# 1wire_connection_board.net
KiCad netlist of a schematic drawn in EAGLE
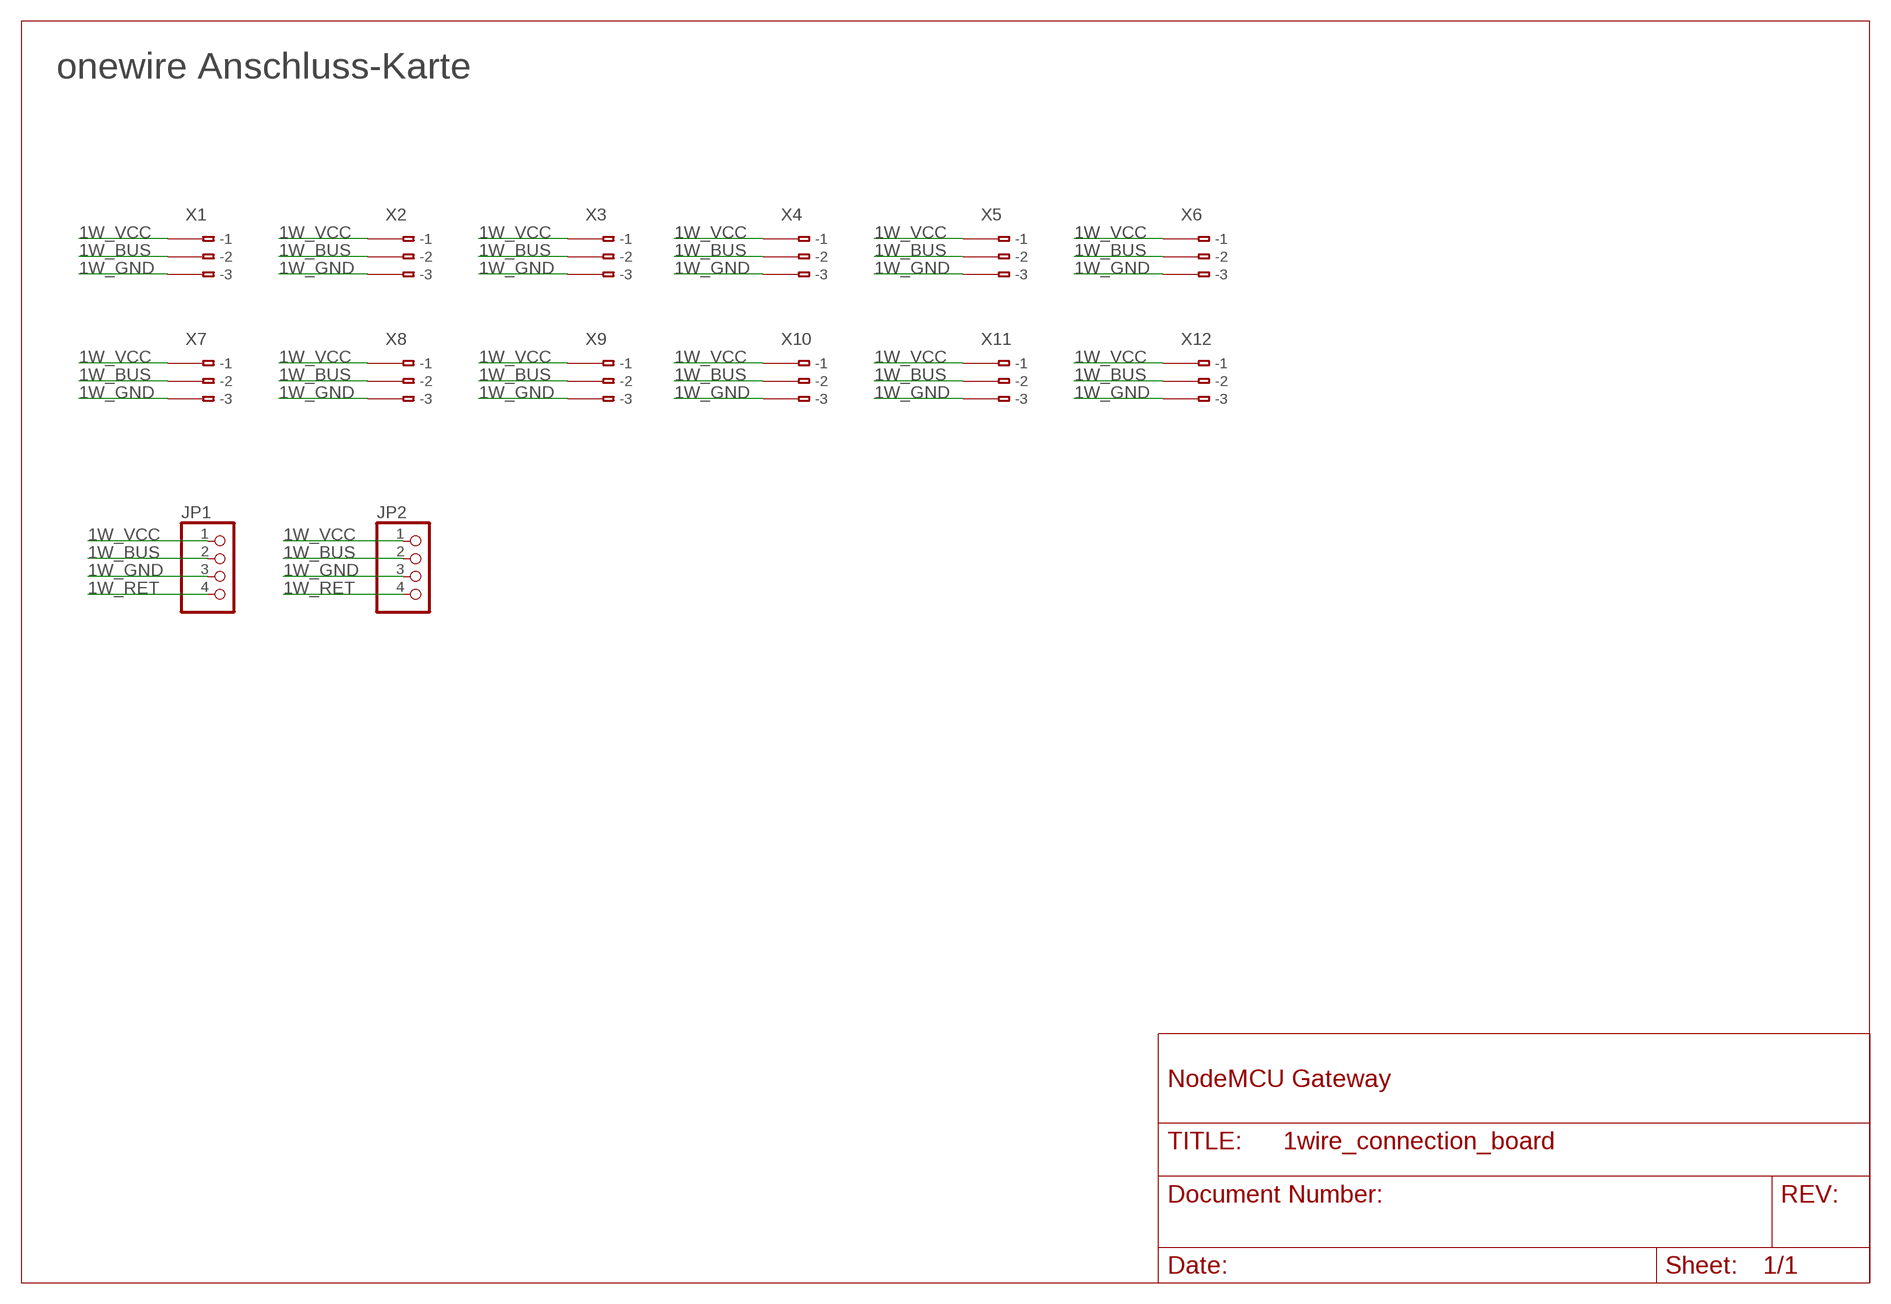
[diagram p0: schematic, sheet 1]

(export (version "E")
  (design (tool "Eeschema 10.0.6"))
  (components
    (comp (ref "JP1")
      (value "PINHD-1X4_S")
      (footprint "eagle-import:1X04")
      (libsource (lib "eagle-import") (part "PINHD-1X4_S"))
    )
    (comp (ref "JP2")
      (value "PINHD-1X4_S")
      (footprint "eagle-import:1X04")
      (libsource (lib "eagle-import") (part "PINHD-1X4_S"))
    )
    (comp (ref "X1")
      (value "CON_350-103")
      (footprint "eagle-import:CON_350-103")
      (fields (field (name "MPN") "233-103"))
      (libsource (lib "eagle-import") (part "CON_350-103"))
    )
    (comp (ref "X2")
      (value "CON_350-103OHNE_RAND")
      (footprint "eagle-import:CON_350-103_O")
      (libsource (lib "eagle-import") (part "CON_350-103OHNE_RAND"))
    )
    (comp (ref "X3")
      (value "CON_350-103OHNE_RAND")
      (footprint "eagle-import:CON_350-103_O")
      (libsource (lib "eagle-import") (part "CON_350-103OHNE_RAND"))
    )
    (comp (ref "X4")
      (value "CON_350-103OHNE_RAND")
      (footprint "eagle-import:CON_350-103_O")
      (libsource (lib "eagle-import") (part "CON_350-103OHNE_RAND"))
    )
    (comp (ref "X5")
      (value "CON_350-103OHNE_RAND")
      (footprint "eagle-import:CON_350-103_O")
      (libsource (lib "eagle-import") (part "CON_350-103OHNE_RAND"))
    )
    (comp (ref "X6")
      (value "CON_350-103OHNE_RAND")
      (footprint "eagle-import:CON_350-103_O")
      (libsource (lib "eagle-import") (part "CON_350-103OHNE_RAND"))
    )
    (comp (ref "X7")
      (value "CON_350-103")
      (footprint "eagle-import:CON_350-103")
      (fields (field (name "MPN") "233-103"))
      (libsource (lib "eagle-import") (part "CON_350-103"))
    )
    (comp (ref "X8")
      (value "CON_350-103OHNE_RAND")
      (footprint "eagle-import:CON_350-103_O")
      (libsource (lib "eagle-import") (part "CON_350-103OHNE_RAND"))
    )
    (comp (ref "X9")
      (value "CON_350-103OHNE_RAND")
      (footprint "eagle-import:CON_350-103_O")
      (libsource (lib "eagle-import") (part "CON_350-103OHNE_RAND"))
    )
    (comp (ref "X10")
      (value "CON_350-103OHNE_RAND")
      (footprint "eagle-import:CON_350-103_O")
      (libsource (lib "eagle-import") (part "CON_350-103OHNE_RAND"))
    )
    (comp (ref "X11")
      (value "CON_350-103OHNE_RAND")
      (footprint "eagle-import:CON_350-103_O")
      (libsource (lib "eagle-import") (part "CON_350-103OHNE_RAND"))
    )
    (comp (ref "X12")
      (value "CON_350-103OHNE_RAND")
      (footprint "eagle-import:CON_350-103_O")
      (libsource (lib "eagle-import") (part "CON_350-103OHNE_RAND"))
    )
  )
  (nets
    (net (code "1") (name "/1W_BUS") (class "Default")
      (node (ref "JP1") (pin "2") (pinfunction "2_2") (pintype "passive"))
      (node (ref "JP2") (pin "2") (pinfunction "2_2") (pintype "passive"))
      (node (ref "X1") (pin "B2") (pinfunction "B-2_B2") (pintype "passive"))
      (node (ref "X10") (pin "B2") (pinfunction "B-2_B2") (pintype "passive"))
      (node (ref "X11") (pin "B2") (pinfunction "B-2_B2") (pintype "passive"))
      (node (ref "X12") (pin "B2") (pinfunction "B-2_B2") (pintype "passive"))
      (node (ref "X2") (pin "B2") (pinfunction "B-2_B2") (pintype "passive"))
      (node (ref "X3") (pin "B2") (pinfunction "B-2_B2") (pintype "passive"))
      (node (ref "X4") (pin "B2") (pinfunction "B-2_B2") (pintype "passive"))
      (node (ref "X5") (pin "B2") (pinfunction "B-2_B2") (pintype "passive"))
      (node (ref "X6") (pin "B2") (pinfunction "B-2_B2") (pintype "passive"))
      (node (ref "X7") (pin "B2") (pinfunction "B-2_B2") (pintype "passive"))
      (node (ref "X8") (pin "B2") (pinfunction "B-2_B2") (pintype "passive"))
      (node (ref "X9") (pin "B2") (pinfunction "B-2_B2") (pintype "passive"))
    )
    (net (code "2") (name "/1W_GND") (class "Default")
      (node (ref "JP1") (pin "3") (pinfunction "3_3") (pintype "passive"))
      (node (ref "JP2") (pin "3") (pinfunction "3_3") (pintype "passive"))
      (node (ref "X1") (pin "B3") (pinfunction "B-3_B3") (pintype "passive"))
      (node (ref "X10") (pin "B3") (pinfunction "B-3_B3") (pintype "passive"))
      (node (ref "X11") (pin "B3") (pinfunction "B-3_B3") (pintype "passive"))
      (node (ref "X12") (pin "B3") (pinfunction "B-3_B3") (pintype "passive"))
      (node (ref "X2") (pin "B3") (pinfunction "B-3_B3") (pintype "passive"))
      (node (ref "X3") (pin "B3") (pinfunction "B-3_B3") (pintype "passive"))
      (node (ref "X4") (pin "B3") (pinfunction "B-3_B3") (pintype "passive"))
      (node (ref "X5") (pin "B3") (pinfunction "B-3_B3") (pintype "passive"))
      (node (ref "X6") (pin "B3") (pinfunction "B-3_B3") (pintype "passive"))
      (node (ref "X7") (pin "B3") (pinfunction "B-3_B3") (pintype "passive"))
      (node (ref "X8") (pin "B3") (pinfunction "B-3_B3") (pintype "passive"))
      (node (ref "X9") (pin "B3") (pinfunction "B-3_B3") (pintype "passive"))
    )
    (net (code "3") (name "/1W_RET") (class "Default")
      (node (ref "JP1") (pin "4") (pinfunction "4_4") (pintype "passive"))
      (node (ref "JP2") (pin "4") (pinfunction "4_4") (pintype "passive"))
    )
    (net (code "4") (name "/1W_VCC") (class "Default")
      (node (ref "JP1") (pin "1") (pinfunction "1_1") (pintype "passive"))
      (node (ref "JP2") (pin "1") (pinfunction "1_1") (pintype "passive"))
      (node (ref "X1") (pin "B1") (pinfunction "B-1_B1") (pintype "passive"))
      (node (ref "X10") (pin "B1") (pinfunction "B-1_B1") (pintype "passive"))
      (node (ref "X11") (pin "B1") (pinfunction "B-1_B1") (pintype "passive"))
      (node (ref "X12") (pin "B1") (pinfunction "B-1_B1") (pintype "passive"))
      (node (ref "X2") (pin "B1") (pinfunction "B-1_B1") (pintype "passive"))
      (node (ref "X3") (pin "B1") (pinfunction "B-1_B1") (pintype "passive"))
      (node (ref "X4") (pin "B1") (pinfunction "B-1_B1") (pintype "passive"))
      (node (ref "X5") (pin "B1") (pinfunction "B-1_B1") (pintype "passive"))
      (node (ref "X6") (pin "B1") (pinfunction "B-1_B1") (pintype "passive"))
      (node (ref "X7") (pin "B1") (pinfunction "B-1_B1") (pintype "passive"))
      (node (ref "X8") (pin "B1") (pinfunction "B-1_B1") (pintype "passive"))
      (node (ref "X9") (pin "B1") (pinfunction "B-1_B1") (pintype "passive"))
    )
    (net (code "5") (name "unconnected-(X1--1-PadA1)") (class "Default")
      (node (ref "X1") (pin "A1") (pinfunction "-1_A1") (pintype "passive"))
    )
    (net (code "6") (name "unconnected-(X1--2-PadA2)") (class "Default")
      (node (ref "X1") (pin "A2") (pinfunction "-2_A2") (pintype "passive"))
    )
    (net (code "7") (name "unconnected-(X1--3-PadA3)") (class "Default")
      (node (ref "X1") (pin "A3") (pinfunction "-3_A3") (pintype "passive"))
    )
    (net (code "8") (name "unconnected-(X2--1-PadA1)") (class "Default")
      (node (ref "X2") (pin "A1") (pinfunction "-1_A1") (pintype "passive"))
    )
    (net (code "9") (name "unconnected-(X2--2-PadA2)") (class "Default")
      (node (ref "X2") (pin "A2") (pinfunction "-2_A2") (pintype "passive"))
    )
    (net (code "10") (name "unconnected-(X2--3-PadA3)") (class "Default")
      (node (ref "X2") (pin "A3") (pinfunction "-3_A3") (pintype "passive"))
    )
    (net (code "11") (name "unconnected-(X3--1-PadA1)") (class "Default")
      (node (ref "X3") (pin "A1") (pinfunction "-1_A1") (pintype "passive"))
    )
    (net (code "12") (name "unconnected-(X3--2-PadA2)") (class "Default")
      (node (ref "X3") (pin "A2") (pinfunction "-2_A2") (pintype "passive"))
    )
    (net (code "13") (name "unconnected-(X3--3-PadA3)") (class "Default")
      (node (ref "X3") (pin "A3") (pinfunction "-3_A3") (pintype "passive"))
    )
    (net (code "14") (name "unconnected-(X4--1-PadA1)") (class "Default")
      (node (ref "X4") (pin "A1") (pinfunction "-1_A1") (pintype "passive"))
    )
    (net (code "15") (name "unconnected-(X4--2-PadA2)") (class "Default")
      (node (ref "X4") (pin "A2") (pinfunction "-2_A2") (pintype "passive"))
    )
    (net (code "16") (name "unconnected-(X4--3-PadA3)") (class "Default")
      (node (ref "X4") (pin "A3") (pinfunction "-3_A3") (pintype "passive"))
    )
    (net (code "17") (name "unconnected-(X5--1-PadA1)") (class "Default")
      (node (ref "X5") (pin "A1") (pinfunction "-1_A1") (pintype "passive"))
    )
    (net (code "18") (name "unconnected-(X5--2-PadA2)") (class "Default")
      (node (ref "X5") (pin "A2") (pinfunction "-2_A2") (pintype "passive"))
    )
    (net (code "19") (name "unconnected-(X5--3-PadA3)") (class "Default")
      (node (ref "X5") (pin "A3") (pinfunction "-3_A3") (pintype "passive"))
    )
    (net (code "20") (name "unconnected-(X6--1-PadA1)") (class "Default")
      (node (ref "X6") (pin "A1") (pinfunction "-1_A1") (pintype "passive"))
    )
    (net (code "21") (name "unconnected-(X6--2-PadA2)") (class "Default")
      (node (ref "X6") (pin "A2") (pinfunction "-2_A2") (pintype "passive"))
    )
    (net (code "22") (name "unconnected-(X6--3-PadA3)") (class "Default")
      (node (ref "X6") (pin "A3") (pinfunction "-3_A3") (pintype "passive"))
    )
    (net (code "23") (name "unconnected-(X7--1-PadA1)") (class "Default")
      (node (ref "X7") (pin "A1") (pinfunction "-1_A1") (pintype "passive"))
    )
    (net (code "24") (name "unconnected-(X7--2-PadA2)") (class "Default")
      (node (ref "X7") (pin "A2") (pinfunction "-2_A2") (pintype "passive"))
    )
    (net (code "25") (name "unconnected-(X7--3-PadA3)") (class "Default")
      (node (ref "X7") (pin "A3") (pinfunction "-3_A3") (pintype "passive"))
    )
    (net (code "26") (name "unconnected-(X8--1-PadA1)") (class "Default")
      (node (ref "X8") (pin "A1") (pinfunction "-1_A1") (pintype "passive"))
    )
    (net (code "27") (name "unconnected-(X8--2-PadA2)") (class "Default")
      (node (ref "X8") (pin "A2") (pinfunction "-2_A2") (pintype "passive"))
    )
    (net (code "28") (name "unconnected-(X8--3-PadA3)") (class "Default")
      (node (ref "X8") (pin "A3") (pinfunction "-3_A3") (pintype "passive"))
    )
    (net (code "29") (name "unconnected-(X9--1-PadA1)") (class "Default")
      (node (ref "X9") (pin "A1") (pinfunction "-1_A1") (pintype "passive"))
    )
    (net (code "30") (name "unconnected-(X9--2-PadA2)") (class "Default")
      (node (ref "X9") (pin "A2") (pinfunction "-2_A2") (pintype "passive"))
    )
    (net (code "31") (name "unconnected-(X9--3-PadA3)") (class "Default")
      (node (ref "X9") (pin "A3") (pinfunction "-3_A3") (pintype "passive"))
    )
    (net (code "32") (name "unconnected-(X10--1-PadA1)") (class "Default")
      (node (ref "X10") (pin "A1") (pinfunction "-1_A1") (pintype "passive"))
    )
    (net (code "33") (name "unconnected-(X10--2-PadA2)") (class "Default")
      (node (ref "X10") (pin "A2") (pinfunction "-2_A2") (pintype "passive"))
    )
    (net (code "34") (name "unconnected-(X10--3-PadA3)") (class "Default")
      (node (ref "X10") (pin "A3") (pinfunction "-3_A3") (pintype "passive"))
    )
    (net (code "35") (name "unconnected-(X11--1-PadA1)") (class "Default")
      (node (ref "X11") (pin "A1") (pinfunction "-1_A1") (pintype "passive"))
    )
    (net (code "36") (name "unconnected-(X11--2-PadA2)") (class "Default")
      (node (ref "X11") (pin "A2") (pinfunction "-2_A2") (pintype "passive"))
    )
    (net (code "37") (name "unconnected-(X11--3-PadA3)") (class "Default")
      (node (ref "X11") (pin "A3") (pinfunction "-3_A3") (pintype "passive"))
    )
    (net (code "38") (name "unconnected-(X12--1-PadA1)") (class "Default")
      (node (ref "X12") (pin "A1") (pinfunction "-1_A1") (pintype "passive"))
    )
    (net (code "39") (name "unconnected-(X12--2-PadA2)") (class "Default")
      (node (ref "X12") (pin "A2") (pinfunction "-2_A2") (pintype "passive"))
    )
    (net (code "40") (name "unconnected-(X12--3-PadA3)") (class "Default")
      (node (ref "X12") (pin "A3") (pinfunction "-3_A3") (pintype "passive"))
    )
  )
)
